# Sheet1.net
KiCad netlist of a schematic drawn in Altium Designer
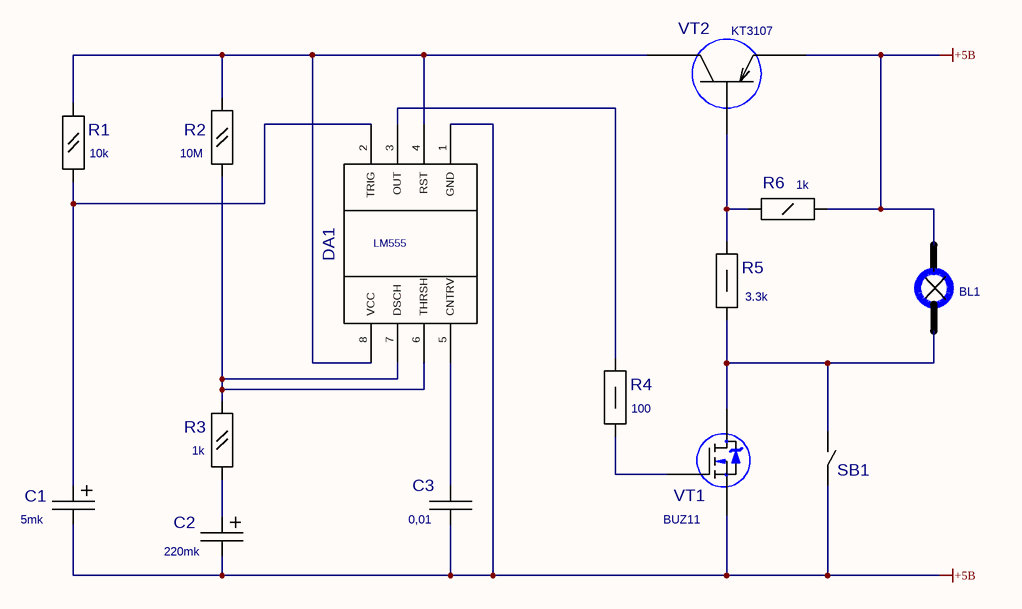
[diagram p0: Sheet1.SCHDOC]

(export (version "E")
  (design (tool "Eeschema 10.0.6"))
  (components
    (comp (ref "BL1") (value "СМН6.3-20-2") (footprint "HL_MINI") (libsource (lib "*") (part "СМН6.3-20-2")))
    (comp (ref "C1")
      (value "5mk")
      (footprint "CE6032_C")
      (description "CE6032-C")
      (libsource (lib "*") (part "CE6032-C"))
    )
    (comp (ref "C2")
      (value "220mk")
      (footprint "CE6032_C")
      (description "CE6032-C")
      (libsource (lib "*") (part "CE6032-C"))
    )
    (comp (ref "C3")
      (value "0,01")
      (footprint "CC2220")
      (description "CC2220")
      (libsource (lib "*") (part "CC2220"))
    )
    (comp (ref "DA1") (value "LM555CM") (footprint "SO-8") (libsource (lib "*") (part "LM555CM")))
    (comp (ref "R1")
      (value "10k")
      (footprint "C2-33H-0.125W")
      (description "C2-33H-0.125W_OLD_UGO")
      (fields (field (name "AUTOR") "pcbdesigner.ru"))
      (libsource (lib "*") (part "C2-33H-0.125W_OLD_UGO"))
    )
    (comp (ref "R2")
      (value "10M")
      (footprint "C2-33H-0.125W")
      (description "C2-33H-0.125W_OLD_UGO")
      (fields (field (name "AUTOR") "pcbdesigner.ru"))
      (libsource (lib "*") (part "C2-33H-0.125W_OLD_UGO"))
    )
    (comp (ref "R3")
      (value "1k")
      (footprint "C2-33H-0.125W")
      (description "C2-33H-0.125W_OLD_UGO")
      (fields (field (name "AUTOR") "pcbdesigner.ru"))
      (libsource (lib "*") (part "C2-33H-0.125W_OLD_UGO"))
    )
    (comp (ref "R4")
      (value "100")
      (footprint "C2-33H-0.5W_15MM")
      (description "C2-33H-0.5W_OLD_UGO")
      (fields (field (name "AUTOR") "pcbdesigner.ru"))
      (libsource (lib "*") (part "C2-33H-0.5W_OLD_UGO"))
    )
    (comp (ref "R5")
      (value "3.3k")
      (footprint "C2-33H-0.5W_15MM")
      (description "C2-33H-0.5W_OLD_UGO")
      (fields (field (name "AUTOR") "pcbdesigner.ru"))
      (libsource (lib "*") (part "C2-33H-0.5W_OLD_UGO"))
    )
    (comp (ref "R6")
      (value "1k")
      (footprint "C2-33H-0.25W")
      (description "C2-33H-0.25W_OLD_UGO")
      (fields (field (name "AUTOR") "pcbdesigner.ru"))
      (libsource (lib "*") (part "C2-33H-0.25W_OLD_UGO"))
    )
    (comp (ref "SB1")
      (value "8AS9M2RE")
      (footprint "8AS9M2RE")
      (fields (field (name "AUTHOR") "pcbdesigner.ru"))
      (libsource (lib "*") (part "8AS9M2RE"))
    )
    (comp (ref "VT1")
      (value "BUZ11")
      (footprint "D2PAK")
      (description "2П771А91")
      (libsource (lib "*") (part "2П771А91"))
    )
    (comp (ref "VT2")
      (value "KT3107")
      (footprint "KT26-1 (2002)")
      (description "KT3107 (2002)")
      (libsource (lib "*") (part "KT3107 (2002)"))
    )
  )
  (nets
    (net (code "1") (name "+5B") (class "Default")
      (node (ref "BL1") (pin "2") (pinfunction "2_2") (pintype "passive"))
      (node (ref "C1") (pin "2") (pinfunction "2_2") (pintype "passive"))
      (node (ref "C2") (pin "2") (pinfunction "2_2") (pintype "passive"))
      (node (ref "C3") (pin "2") (pinfunction "2_2") (pintype "passive"))
      (node (ref "DA1") (pin "1") (pinfunction "GND_1") (pintype "passive"))
      (node (ref "R6") (pin "2") (pinfunction "2_2") (pintype "passive"))
      (node (ref "SB1") (pin "2") (pinfunction "2_2") (pintype "passive"))
      (node (ref "VT1") (pin "3") (pinfunction "2_3") (pintype "passive"))
      (node (ref "VT2") (pin "3") (pinfunction "E_3") (pintype "passive"))
    )
    (net (code "2") (name "Net-(C2-Pad1)") (class "Default")
      (node (ref "C2") (pin "1") (pinfunction "1_1") (pintype "passive"))
      (node (ref "R3") (pin "1") (pinfunction "1_1") (pintype "passive"))
    )
    (net (code "3") (name "Net-(DA1-CNTRV)") (class "Default")
      (node (ref "C3") (pin "1") (pinfunction "1_1") (pintype "passive"))
      (node (ref "DA1") (pin "5") (pinfunction "CNTRV_5") (pintype "passive"))
    )
    (net (code "4") (name "Net-(DA1-DSCH)") (class "Default")
      (node (ref "DA1") (pin "6") (pinfunction "THRSH_6") (pintype "passive"))
      (node (ref "DA1") (pin "7") (pinfunction "DSCH_7") (pintype "passive"))
      (node (ref "R2") (pin "1") (pinfunction "1_1") (pintype "passive"))
      (node (ref "R3") (pin "2") (pinfunction "2_2") (pintype "passive"))
    )
    (net (code "5") (name "Net-(DA1-OUT)") (class "Default")
      (node (ref "DA1") (pin "3") (pinfunction "OUT_3") (pintype "passive"))
      (node (ref "R4") (pin "2") (pinfunction "2_2") (pintype "passive"))
    )
    (net (code "6") (name "Net-(DA1-RST)") (class "Default")
      (node (ref "DA1") (pin "4") (pinfunction "RST_4") (pintype "passive"))
      (node (ref "DA1") (pin "8") (pinfunction "VCC_8") (pintype "passive"))
      (node (ref "R1") (pin "2") (pinfunction "2_2") (pintype "passive"))
      (node (ref "R2") (pin "2") (pinfunction "2_2") (pintype "passive"))
      (node (ref "VT2") (pin "1") (pinfunction "K_1") (pintype "passive"))
    )
    (net (code "7") (name "Net-(DA1-TRIG)") (class "Default")
      (node (ref "C1") (pin "1") (pinfunction "1_1") (pintype "passive"))
      (node (ref "DA1") (pin "2") (pinfunction "TRIG_2") (pintype "passive"))
      (node (ref "R1") (pin "1") (pinfunction "1_1") (pintype "passive"))
    )
    (net (code "8") (name "Net-(R4-Pad1)") (class "Default")
      (node (ref "R4") (pin "1") (pinfunction "1_1") (pintype "passive"))
      (node (ref "VT1") (pin "1") (pinfunction "1_1") (pintype "passive"))
    )
    (net (code "9") (name "Net-(VT1-3)") (class "Default")
      (node (ref "BL1") (pin "1") (pinfunction "1_1") (pintype "passive"))
      (node (ref "R5") (pin "1") (pinfunction "1_1") (pintype "passive"))
      (node (ref "SB1") (pin "1") (pinfunction "1_1") (pintype "passive"))
      (node (ref "VT1") (pin "2") (pinfunction "3_2") (pintype "passive"))
    )
    (net (code "10") (name "Net-(VT2-B)") (class "Default")
      (node (ref "R5") (pin "2") (pinfunction "2_2") (pintype "passive"))
      (node (ref "R6") (pin "1") (pinfunction "1_1") (pintype "passive"))
      (node (ref "VT2") (pin "2") (pinfunction "B_2") (pintype "passive"))
    )
  )
)
